# DASH_CAN.net
KiCad netlist of a schematic drawn in Altium Designer
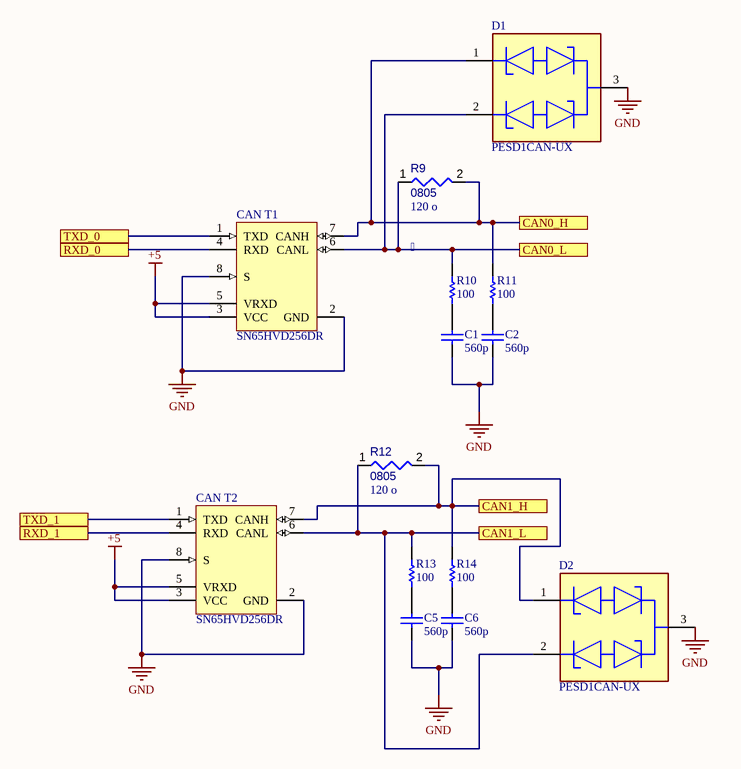
[diagram p0: DASH_CAN.SchDoc]

(export (version "E")
  (design (tool "Eeschema 10.0.6"))
  (components
    (comp (ref "C1")
      (value "560p")
      (footprint "CAPC1608X87X35NL15T15")
      (description ".1 uf")
      (fields (field (name "PART NUMBER") "C0603C104J3RAC7867") (field (name "MANUFACTURER") "Kemet"))
      (libsource (lib "Altium Content Vault") (part "CAP"))
    )
    (comp (ref "C2")
      (value "560p")
      (footprint "CAPC1608X87X35NL15T15")
      (description ".1 uf")
      (fields (field (name "PART NUMBER") "C0603C104J3RAC7867") (field (name "MANUFACTURER") "Kemet"))
      (libsource (lib "Altium Content Vault") (part "CAP"))
    )
    (comp (ref "C5")
      (value "560p")
      (footprint "CAPC1608X87X35NL15T15")
      (description ".1 uf")
      (fields (field (name "PART NUMBER") "C0603C104J3RAC7867") (field (name "MANUFACTURER") "Kemet"))
      (libsource (lib "Altium Content Vault") (part "CAP"))
    )
    (comp (ref "C6")
      (value "560p")
      (footprint "CAPC1608X87X35NL15T15")
      (description ".1 uf")
      (fields (field (name "PART NUMBER") "C0603C104J3RAC7867") (field (name "MANUFACTURER") "Kemet"))
      (libsource (lib "Altium Content Vault") (part "CAP"))
    )
    (comp (ref "CAN T1")
      (value "SN65HVD256DR")
      (footprint "D0008A_L")
      (fields (field (name "MANUFACTURER") "Texas Instruments"))
      (libsource (lib "Altium Content Vault") (part "TI-SN65HVD256-SOIC_D-8"))
    )
    (comp (ref "CAN T2")
      (value "SN65HVD256DR")
      (footprint "D0008A_L")
      (fields (field (name "MANUFACTURER") "Texas Instruments"))
      (libsource (lib "Altium Content Vault") (part "TI-SN65HVD256-SOIC_D-8"))
    )
    (comp (ref "D1")
      (value "PESD1CAN-UX")
      (footprint "FP-SOT323-MFG")
      (description "TVS DIODE 24V 50V SC70-3")
      (libsource (lib "Altium Content Vault") (part "04d57993b6b7b0f5b3c95ba4f97dea0"))
    )
    (comp (ref "D2")
      (value "PESD1CAN-UX")
      (footprint "FP-SOT323-MFG")
      (description "TVS DIODE 24V 50V SC70-3")
      (libsource (lib "Altium Content Vault") (part "04d57993b6b7b0f5b3c95ba4f97dea0"))
    )
    (comp (ref "R9")
      (value "0805")
      (footprint "RESC0805(2012)_L")
      (description "Chip Resistor, 4,7 Ohms, +/-5 %, 125 mW, -55 to 155 degC, 0805")
      (fields
        (field (name "ALTIUM_VALUE") "120 o")
        (field (name "MAX OPERATING TEMPERATURE") "")
        (field (name "AVAILABLE PREVIEW IMAGES") "2D")
      )
      (libsource (lib "") (part "Symbol_1"))
    )
    (comp (ref "R10")
      (value "100")
      (footprint "RESC1608X55X25ML10T15")
      (description "Chip Resistor, 0 Ohm, 0.1 W, -55 to 155 degC, 0603 (1608 Metric)")
      (libsource (lib "Illini Formula Electric") (part "Symbol"))
    )
    (comp (ref "R11")
      (value "100")
      (footprint "RESC1608X55X25ML10T15")
      (description "Chip Resistor, 0 Ohm, 0.1 W, -55 to 155 degC, 0603 (1608 Metric)")
      (libsource (lib "Illini Formula Electric") (part "Symbol"))
    )
    (comp (ref "R12")
      (value "0805")
      (footprint "RESC0805(2012)_L")
      (description "Chip Resistor, 4,7 Ohms, +/-5 %, 125 mW, -55 to 155 degC, 0805")
      (fields (field (name "ALTIUM_VALUE") "120 o") (field (name "AVAILABLE PREVIEW IMAGES") "2D"))
      (libsource (lib "") (part "Symbol_1"))
    )
    (comp (ref "R13")
      (value "100")
      (footprint "RESC1608X55X25ML10T15")
      (description "Chip Resistor, 0 Ohm, 0.1 W, -55 to 155 degC, 0603 (1608 Metric)")
      (libsource (lib "Illini Formula Electric") (part "Symbol"))
    )
    (comp (ref "R14")
      (value "100")
      (footprint "RESC1608X55X25ML10T15")
      (description "Chip Resistor, 0 Ohm, 0.1 W, -55 to 155 degC, 0603 (1608 Metric)")
      (libsource (lib "Illini Formula Electric") (part "Symbol"))
    )
  )
  (nets
    (net (code "1") (name "+5") (class "Default")
      (node (ref "CAN T1") (pin "3") (pinfunction "VCC_3") (pintype "power_in"))
      (node (ref "CAN T1") (pin "5") (pinfunction "VRXD_5") (pintype "power_in"))
      (node (ref "CAN T2") (pin "3") (pinfunction "VCC_3") (pintype "power_in"))
      (node (ref "CAN T2") (pin "5") (pinfunction "VRXD_5") (pintype "power_in"))
    )
    (net (code "2") (name "/CAN0_H") (class "Default")
      (node (ref "CAN T1") (pin "7") (pinfunction "CANH_7") (pintype "bidirectional"))
      (node (ref "D1") (pin "1") (pinfunction "cathode_1_1") (pintype "passive"))
      (node (ref "R11") (pin "2") (pinfunction "2_2") (pintype "passive"))
      (node (ref "R9") (pin "2") (pinfunction "2_2") (pintype "passive"))
    )
    (net (code "3") (name "/CAN0_L") (class "Default")
      (node (ref "CAN T1") (pin "6") (pinfunction "CANL_6") (pintype "bidirectional"))
      (node (ref "D1") (pin "2") (pinfunction "cathode_2_2") (pintype "passive"))
      (node (ref "R10") (pin "2") (pinfunction "2_2") (pintype "passive"))
      (node (ref "R9") (pin "1") (pinfunction "1_1") (pintype "passive"))
    )
    (net (code "4") (name "/CAN1_H") (class "Default")
      (node (ref "CAN T2") (pin "7") (pinfunction "CANH_7") (pintype "bidirectional"))
      (node (ref "D2") (pin "1") (pinfunction "cathode_1_1") (pintype "passive"))
      (node (ref "R12") (pin "2") (pinfunction "2_2") (pintype "passive"))
      (node (ref "R14") (pin "2") (pinfunction "2_2") (pintype "passive"))
    )
    (net (code "5") (name "/CAN1_L") (class "Default")
      (node (ref "CAN T2") (pin "6") (pinfunction "CANL_6") (pintype "bidirectional"))
      (node (ref "D2") (pin "2") (pinfunction "cathode_2_2") (pintype "passive"))
      (node (ref "R12") (pin "1") (pinfunction "1_1") (pintype "passive"))
      (node (ref "R13") (pin "2") (pinfunction "2_2") (pintype "passive"))
    )
    (net (code "6") (name "/RXD_0") (class "Default")
      (node (ref "CAN T1") (pin "4") (pinfunction "RXD_4") (pintype "tri_state"))
    )
    (net (code "7") (name "/RXD_1") (class "Default")
      (node (ref "CAN T2") (pin "4") (pinfunction "RXD_4") (pintype "tri_state"))
    )
    (net (code "8") (name "/TXD_0") (class "Default")
      (node (ref "CAN T1") (pin "1") (pinfunction "TXD_1") (pintype "input"))
    )
    (net (code "9") (name "/TXD_1") (class "Default")
      (node (ref "CAN T2") (pin "1") (pinfunction "TXD_1") (pintype "input"))
    )
    (net (code "10") (name "GND") (class "Default")
      (node (ref "C1") (pin "1") (pinfunction "1_1") (pintype "passive"))
      (node (ref "C2") (pin "1") (pinfunction "1_1") (pintype "passive"))
      (node (ref "C5") (pin "1") (pinfunction "1_1") (pintype "passive"))
      (node (ref "C6") (pin "1") (pinfunction "1_1") (pintype "passive"))
      (node (ref "CAN T1") (pin "2") (pinfunction "GND_2") (pintype "power_in"))
      (node (ref "CAN T1") (pin "8") (pinfunction "S_8") (pintype "input"))
      (node (ref "CAN T2") (pin "2") (pinfunction "GND_2") (pintype "power_in"))
      (node (ref "CAN T2") (pin "8") (pinfunction "S_8") (pintype "input"))
      (node (ref "D1") (pin "3") (pinfunction "common_cathode_3") (pintype "passive"))
      (node (ref "D2") (pin "3") (pinfunction "common_cathode_3") (pintype "passive"))
    )
    (net (code "11") (name "Net-(C1-Pad2)") (class "Default")
      (node (ref "C1") (pin "2") (pinfunction "2_2") (pintype "passive"))
      (node (ref "R10") (pin "1") (pinfunction "1_1") (pintype "passive"))
    )
    (net (code "12") (name "Net-(C2-Pad2)") (class "Default")
      (node (ref "C2") (pin "2") (pinfunction "2_2") (pintype "passive"))
      (node (ref "R11") (pin "1") (pinfunction "1_1") (pintype "passive"))
    )
    (net (code "13") (name "Net-(C5-Pad2)") (class "Default")
      (node (ref "C5") (pin "2") (pinfunction "2_2") (pintype "passive"))
      (node (ref "R13") (pin "1") (pinfunction "1_1") (pintype "passive"))
    )
    (net (code "14") (name "Net-(C6-Pad2)") (class "Default")
      (node (ref "C6") (pin "2") (pinfunction "2_2") (pintype "passive"))
      (node (ref "R14") (pin "1") (pinfunction "1_1") (pintype "passive"))
    )
  )
)
